# Spike_and_Hold_V2_2.net
KiCad netlist of a schematic drawn in Altium Designer
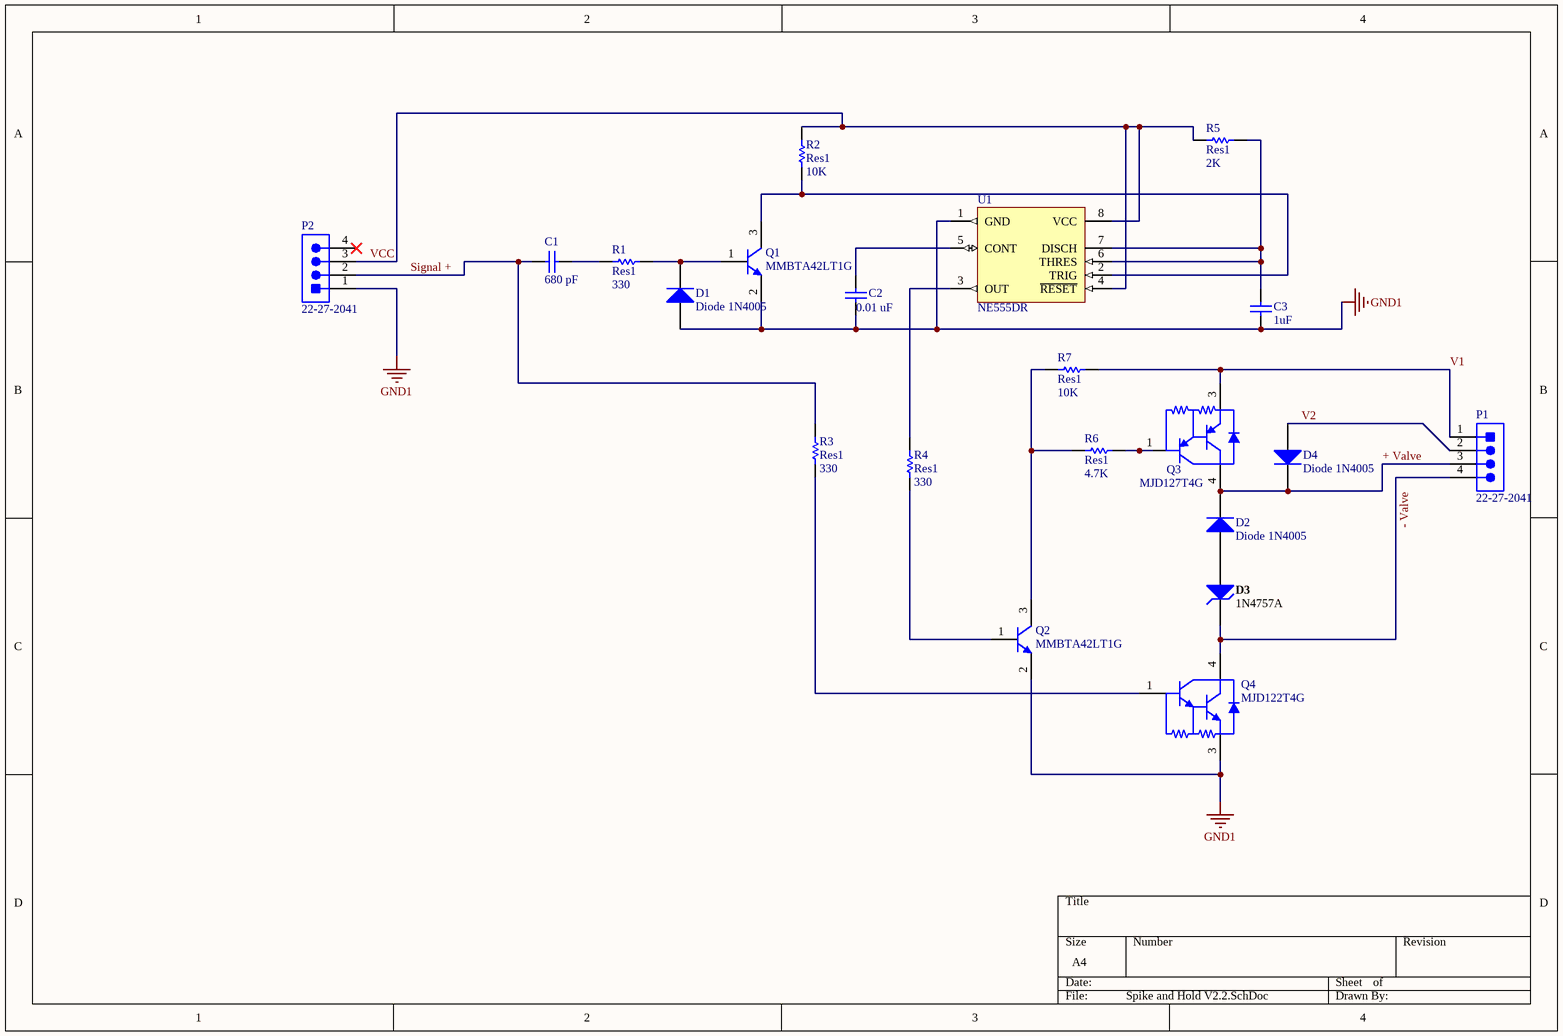
[diagram p0: Spike and Hold V2.2.SchDoc]

(export (version "E")
  (design (tool "Eeschema 10.0.6"))
  (components
    (comp (ref "C1")
      (value "680 pF")
      (footprint "CAPC1005X55X30LL05T10")
      (fields (field (name "PART NUMBER") "C0402C681K5RACTU") (field (name "MANUFACTURER") "Kemet"))
      (libsource (lib "Altium Content Vault") (part "CAP"))
    )
    (comp (ref "C2")
      (value "0.01 uF")
      (footprint "CAPC1608X87X35LL15T15")
      (fields (field (name "PART NUMBER") "C0603C103K5RACTU") (field (name "MANUFACTURER") "Kemet"))
      (libsource (lib "Altium Content Vault") (part "CMP-2006-03044-1"))
    )
    (comp (ref "C3")
      (value "1uF")
      (footprint "CAPC1206(3216)110_L")
      (description "CAP 1uF 50V ±10% 1206 (3216 Metric) Thickness 1.1mm SMD")
      (fields (field (name "TOLERANCE") "Â±10%"))
      (libsource (lib "Altium Content Vault") (part "CAP"))
    )
    (comp (ref "D1")
      (value "Diode 1N4005")
      (footprint "DO-41")
      (description "1 Amp General Purpose Rectifier")
      (fields (field (name "PUBLISHER") "Altium Limited"))
      (libsource (lib "Miscellaneous Devices") (part "Diode 1N4005"))
    )
    (comp (ref "D2")
      (value "Diode 1N4005")
      (footprint "DO-41")
      (description "1 Amp General Purpose Rectifier")
      (fields (field (name "PUBLISHER") "Altium Limited"))
      (libsource (lib "Miscellaneous Devices") (part "Diode 1N4005"))
    )
    (comp (ref "D3")
      (value "1N4757A")
      (footprint "FAIR-DO-41-2_V")
      (description "Zener Diode, 51V, 1W, 5%, -65 to 200 degC, 2-Pin DO-41, Body 2.72 x 5.2 mm, RoHS")
      (fields (field (name "MANUFACTURER") "Fairchild Semiconductor") (field (name "TOLERANCE") "5%"))
      (libsource (lib "Altium Content Vault") (part "FAIR-DZEN-A1K2-2"))
    )
    (comp (ref "D4")
      (value "Diode 1N4005")
      (footprint "DO-41")
      (description "1 Amp General Purpose Rectifier")
      (fields (field (name "PUBLISHER") "Altium Limited"))
      (libsource (lib "Miscellaneous Devices") (part "Diode 1N4005"))
    )
    (comp (ref "P1")
      (value "22-27-2041")
      (footprint "MOLX-22-27-2041_V")
      (description "Male Header, Pitch 2.54 mm, 1 x 4 Position, Height 11.7 mm, Tail Length 3.56 mm, RoHS, Bulk")
      (fields (field (name "MANUFACTURER") "Molex"))
      (libsource (lib "Altium Content Vault") (part "CN-1P-M-R4"))
    )
    (comp (ref "P2")
      (value "22-27-2041")
      (footprint "MOLX-22-27-2041_V")
      (description "Male Header, Pitch 2.54 mm, 1 x 4 Position, Height 11.7 mm, Tail Length 3.56 mm, RoHS, Bulk")
      (fields (field (name "MANUFACTURER") "Molex"))
      (libsource (lib "") (part "CN-1P-M-R4_1"))
    )
    (comp (ref "Q1")
      (value "MMBTA42LT1G")
      (footprint "ONSC-SOT-23-3-318-08_V")
      (description "High Voltage Transistor, NPN Silicon, 3-Pin SOT-23, Pb-Free, Tape and Reel")
      (fields (field (name "MANUFACTURER") "On Semiconductor"))
      (libsource (lib "Altium Content Vault") (part "CMP-1048-00662-1"))
    )
    (comp (ref "Q2")
      (value "MMBTA42LT1G")
      (footprint "ONSC-SOT-23-3-318-08_V")
      (description "High Voltage Transistor, NPN Silicon, 3-Pin SOT-23, Pb-Free, Tape and Reel")
      (fields (field (name "MANUFACTURER") "On Semiconductor"))
      (libsource (lib "Altium Content Vault") (part "CMP-1048-00662-1"))
    )
    (comp (ref "Q3")
      (value "MJD127T4G")
      (footprint "ONSC-DPAK-3-369C-01_V")
      (description "Complementary Darlington Power Transistor, 3-Pin DPAK, Pb-Free, Tape and Reel")
      (fields (field (name "MANUFACTURER") "On Semiconductor"))
      (libsource (lib "Altium Content Vault") (part "CMP-1047-00009-1"))
    )
    (comp (ref "Q4")
      (value "MJD122T4G")
      (footprint "ONSC-DPAK-3-369C-01_V")
      (description "Complementary Darlington Power Transistor, 3-Pin DPAK, Pb-Free, Tape and Reel")
      (fields (field (name "MANUFACTURER") "On Semiconductor"))
      (libsource (lib "Altium Content Vault") (part "CMP-1047-00007-1"))
    )
    (comp (ref "R1")
      (value "Res1")
      (footprint "AXIAL-0.3")
      (description "Resistor")
      (fields (field (name "ALTIUM_VALUE") "330") (field (name "PUBLISHER") "Altium Limited"))
      (libsource (lib "Miscellaneous Devices") (part "Res1"))
    )
    (comp (ref "R2")
      (value "Res1")
      (footprint "AXIAL-0.3")
      (description "Resistor")
      (fields (field (name "ALTIUM_VALUE") "10K") (field (name "PUBLISHER") "Altium Limited"))
      (libsource (lib "Miscellaneous Devices") (part "Res1"))
    )
    (comp (ref "R3")
      (value "Res1")
      (footprint "AXIAL-0.3")
      (description "Resistor")
      (fields (field (name "ALTIUM_VALUE") "330") (field (name "PUBLISHER") "Altium Limited"))
      (libsource (lib "Miscellaneous Devices") (part "Res1"))
    )
    (comp (ref "R4")
      (value "Res1")
      (footprint "AXIAL-0.3")
      (description "Resistor")
      (fields (field (name "ALTIUM_VALUE") "330") (field (name "PUBLISHER") "Altium Limited"))
      (libsource (lib "Miscellaneous Devices") (part "Res1"))
    )
    (comp (ref "R5")
      (value "Res1")
      (footprint "AXIAL-0.3")
      (description "Resistor")
      (fields (field (name "ALTIUM_VALUE") "2K") (field (name "PUBLISHER") "Altium Limited"))
      (libsource (lib "Miscellaneous Devices") (part "Res1"))
    )
    (comp (ref "R6")
      (value "Res1")
      (footprint "AXIAL-0.3")
      (description "Resistor")
      (fields (field (name "ALTIUM_VALUE") "4.7K") (field (name "PUBLISHER") "Altium Limited"))
      (libsource (lib "Miscellaneous Devices") (part "Res1"))
    )
    (comp (ref "R7")
      (value "Res1")
      (footprint "AXIAL-0.3")
      (description "Resistor")
      (fields (field (name "ALTIUM_VALUE") "10K") (field (name "PUBLISHER") "Altium Limited"))
      (libsource (lib "Miscellaneous Devices") (part "Res1"))
    )
    (comp (ref "U1")
      (value "NE555DR")
      (footprint "D0008A_L")
      (libsource (lib "Altium Content Vault") (part "CMP-1685-00007-1"))
    )
  )
  (nets
    (net (code "1") (name "/+ Valve") (class "Default")
      (node (ref "D2") (pin "2") (pinfunction "K_2") (pintype "passive"))
      (node (ref "D4") (pin "2") (pinfunction "K_2") (pintype "passive"))
      (node (ref "P1") (pin "3") (pinfunction "3_3") (pintype "passive"))
      (node (ref "Q3") (pin "4") (pinfunction "C_4") (pintype "passive"))
    )
    (net (code "2") (name "/- Valve") (class "Default")
      (node (ref "D3") (pin "2") (pinfunction "K_2") (pintype "passive"))
      (node (ref "P1") (pin "4") (pinfunction "4_4") (pintype "passive"))
      (node (ref "Q4") (pin "4") (pinfunction "C_4") (pintype "passive"))
    )
    (net (code "3") (name "/Signal +") (class "Default")
      (node (ref "C1") (pin "1") (pinfunction "1_1") (pintype "passive"))
      (node (ref "P2") (pin "2") (pinfunction "2_2") (pintype "passive"))
      (node (ref "R3") (pin "2") (pinfunction "2_2") (pintype "passive"))
    )
    (net (code "4") (name "/V1") (class "Default")
      (node (ref "P1") (pin "1") (pinfunction "1_1") (pintype "passive"))
      (node (ref "Q3") (pin "3") (pinfunction "E_3") (pintype "passive"))
      (node (ref "R7") (pin "2") (pinfunction "2_2") (pintype "passive"))
    )
    (net (code "5") (name "/V2") (class "Default")
      (node (ref "D4") (pin "1") (pinfunction "A_1") (pintype "passive"))
      (node (ref "P1") (pin "2") (pinfunction "2_2") (pintype "passive"))
    )
    (net (code "6") (name "/VCC") (class "Default")
      (node (ref "P2") (pin "3") (pinfunction "3_3") (pintype "passive"))
      (node (ref "R2") (pin "2") (pinfunction "2_2") (pintype "passive"))
      (node (ref "R5") (pin "1") (pinfunction "1_1") (pintype "passive"))
      (node (ref "U1") (pin "4") (pinfunction "~{RESET}_4") (pintype "input"))
      (node (ref "U1") (pin "8") (pinfunction "VCC_8") (pintype "power_in"))
    )
    (net (code "7") (name "GND1") (class "Default")
      (node (ref "C2") (pin "1") (pinfunction "1_1") (pintype "passive"))
      (node (ref "C3") (pin "1") (pinfunction "1_1") (pintype "passive"))
      (node (ref "D1") (pin "1") (pinfunction "A_1") (pintype "passive"))
      (node (ref "P2") (pin "1") (pinfunction "1_1") (pintype "passive"))
      (node (ref "Q1") (pin "2") (pinfunction "E_2") (pintype "passive"))
      (node (ref "Q2") (pin "2") (pinfunction "E_2") (pintype "passive"))
      (node (ref "Q4") (pin "3") (pinfunction "E_3") (pintype "passive"))
      (node (ref "U1") (pin "1") (pinfunction "GND_1") (pintype "output"))
    )
    (net (code "8") (name "Net-(C1-Pad2)") (class "Default")
      (node (ref "C1") (pin "2") (pinfunction "2_2") (pintype "passive"))
      (node (ref "R1") (pin "1") (pinfunction "1_1") (pintype "passive"))
    )
    (net (code "9") (name "Net-(D1-K)") (class "Default")
      (node (ref "D1") (pin "2") (pinfunction "K_2") (pintype "passive"))
      (node (ref "Q1") (pin "1") (pinfunction "B_1") (pintype "passive"))
      (node (ref "R1") (pin "2") (pinfunction "2_2") (pintype "passive"))
    )
    (net (code "10") (name "Net-(D2-A)") (class "Default")
      (node (ref "D2") (pin "1") (pinfunction "A_1") (pintype "passive"))
      (node (ref "D3") (pin "1") (pinfunction "A_1") (pintype "passive"))
    )
    (net (code "11") (name "Net-(Q1-C)") (class "Default")
      (node (ref "Q1") (pin "3") (pinfunction "C_3") (pintype "passive"))
      (node (ref "R2") (pin "1") (pinfunction "1_1") (pintype "passive"))
      (node (ref "U1") (pin "2") (pinfunction "TRIG_2") (pintype "input"))
    )
    (net (code "12") (name "Net-(Q2-B)") (class "Default")
      (node (ref "Q2") (pin "1") (pinfunction "B_1") (pintype "passive"))
      (node (ref "R4") (pin "1") (pinfunction "1_1") (pintype "passive"))
    )
    (net (code "13") (name "Net-(Q2-C)") (class "Default")
      (node (ref "Q2") (pin "3") (pinfunction "C_3") (pintype "passive"))
      (node (ref "R6") (pin "1") (pinfunction "1_1") (pintype "passive"))
      (node (ref "R7") (pin "1") (pinfunction "1_1") (pintype "passive"))
    )
    (net (code "14") (name "Net-(Q3-B)") (class "Default")
      (node (ref "Q3") (pin "1") (pinfunction "B_1") (pintype "passive"))
      (node (ref "R6") (pin "2") (pinfunction "2_2") (pintype "passive"))
    )
    (net (code "15") (name "Net-(Q4-B)") (class "Default")
      (node (ref "Q4") (pin "1") (pinfunction "B_1") (pintype "passive"))
      (node (ref "R3") (pin "1") (pinfunction "1_1") (pintype "passive"))
    )
    (net (code "16") (name "Net-(U1-CONT)") (class "Default")
      (node (ref "C2") (pin "2") (pinfunction "2_2") (pintype "passive"))
      (node (ref "U1") (pin "5") (pinfunction "CONT_5") (pintype "bidirectional"))
    )
    (net (code "17") (name "Net-(U1-DISCH)") (class "Default")
      (node (ref "C3") (pin "2") (pinfunction "2_2") (pintype "passive"))
      (node (ref "R5") (pin "2") (pinfunction "2_2") (pintype "passive"))
      (node (ref "U1") (pin "6") (pinfunction "THRES_6") (pintype "input"))
      (node (ref "U1") (pin "7") (pinfunction "DISCH_7") (pintype "open_collector"))
    )
    (net (code "18") (name "Net-(U1-OUT)") (class "Default")
      (node (ref "R4") (pin "2") (pinfunction "2_2") (pintype "passive"))
      (node (ref "U1") (pin "3") (pinfunction "OUT_3") (pintype "output"))
    )
    (net (code "19") (name "unconnected-(P2-Pad4)") (class "Default")
      (node (ref "P2") (pin "4") (pinfunction "4_4") (pintype "passive+no_connect"))
    )
  )
)
